# SCH_Victron-Orion-DC-DC-Charger-Cooling-.net
KiCad netlist of a schematic drawn in EasyEDA
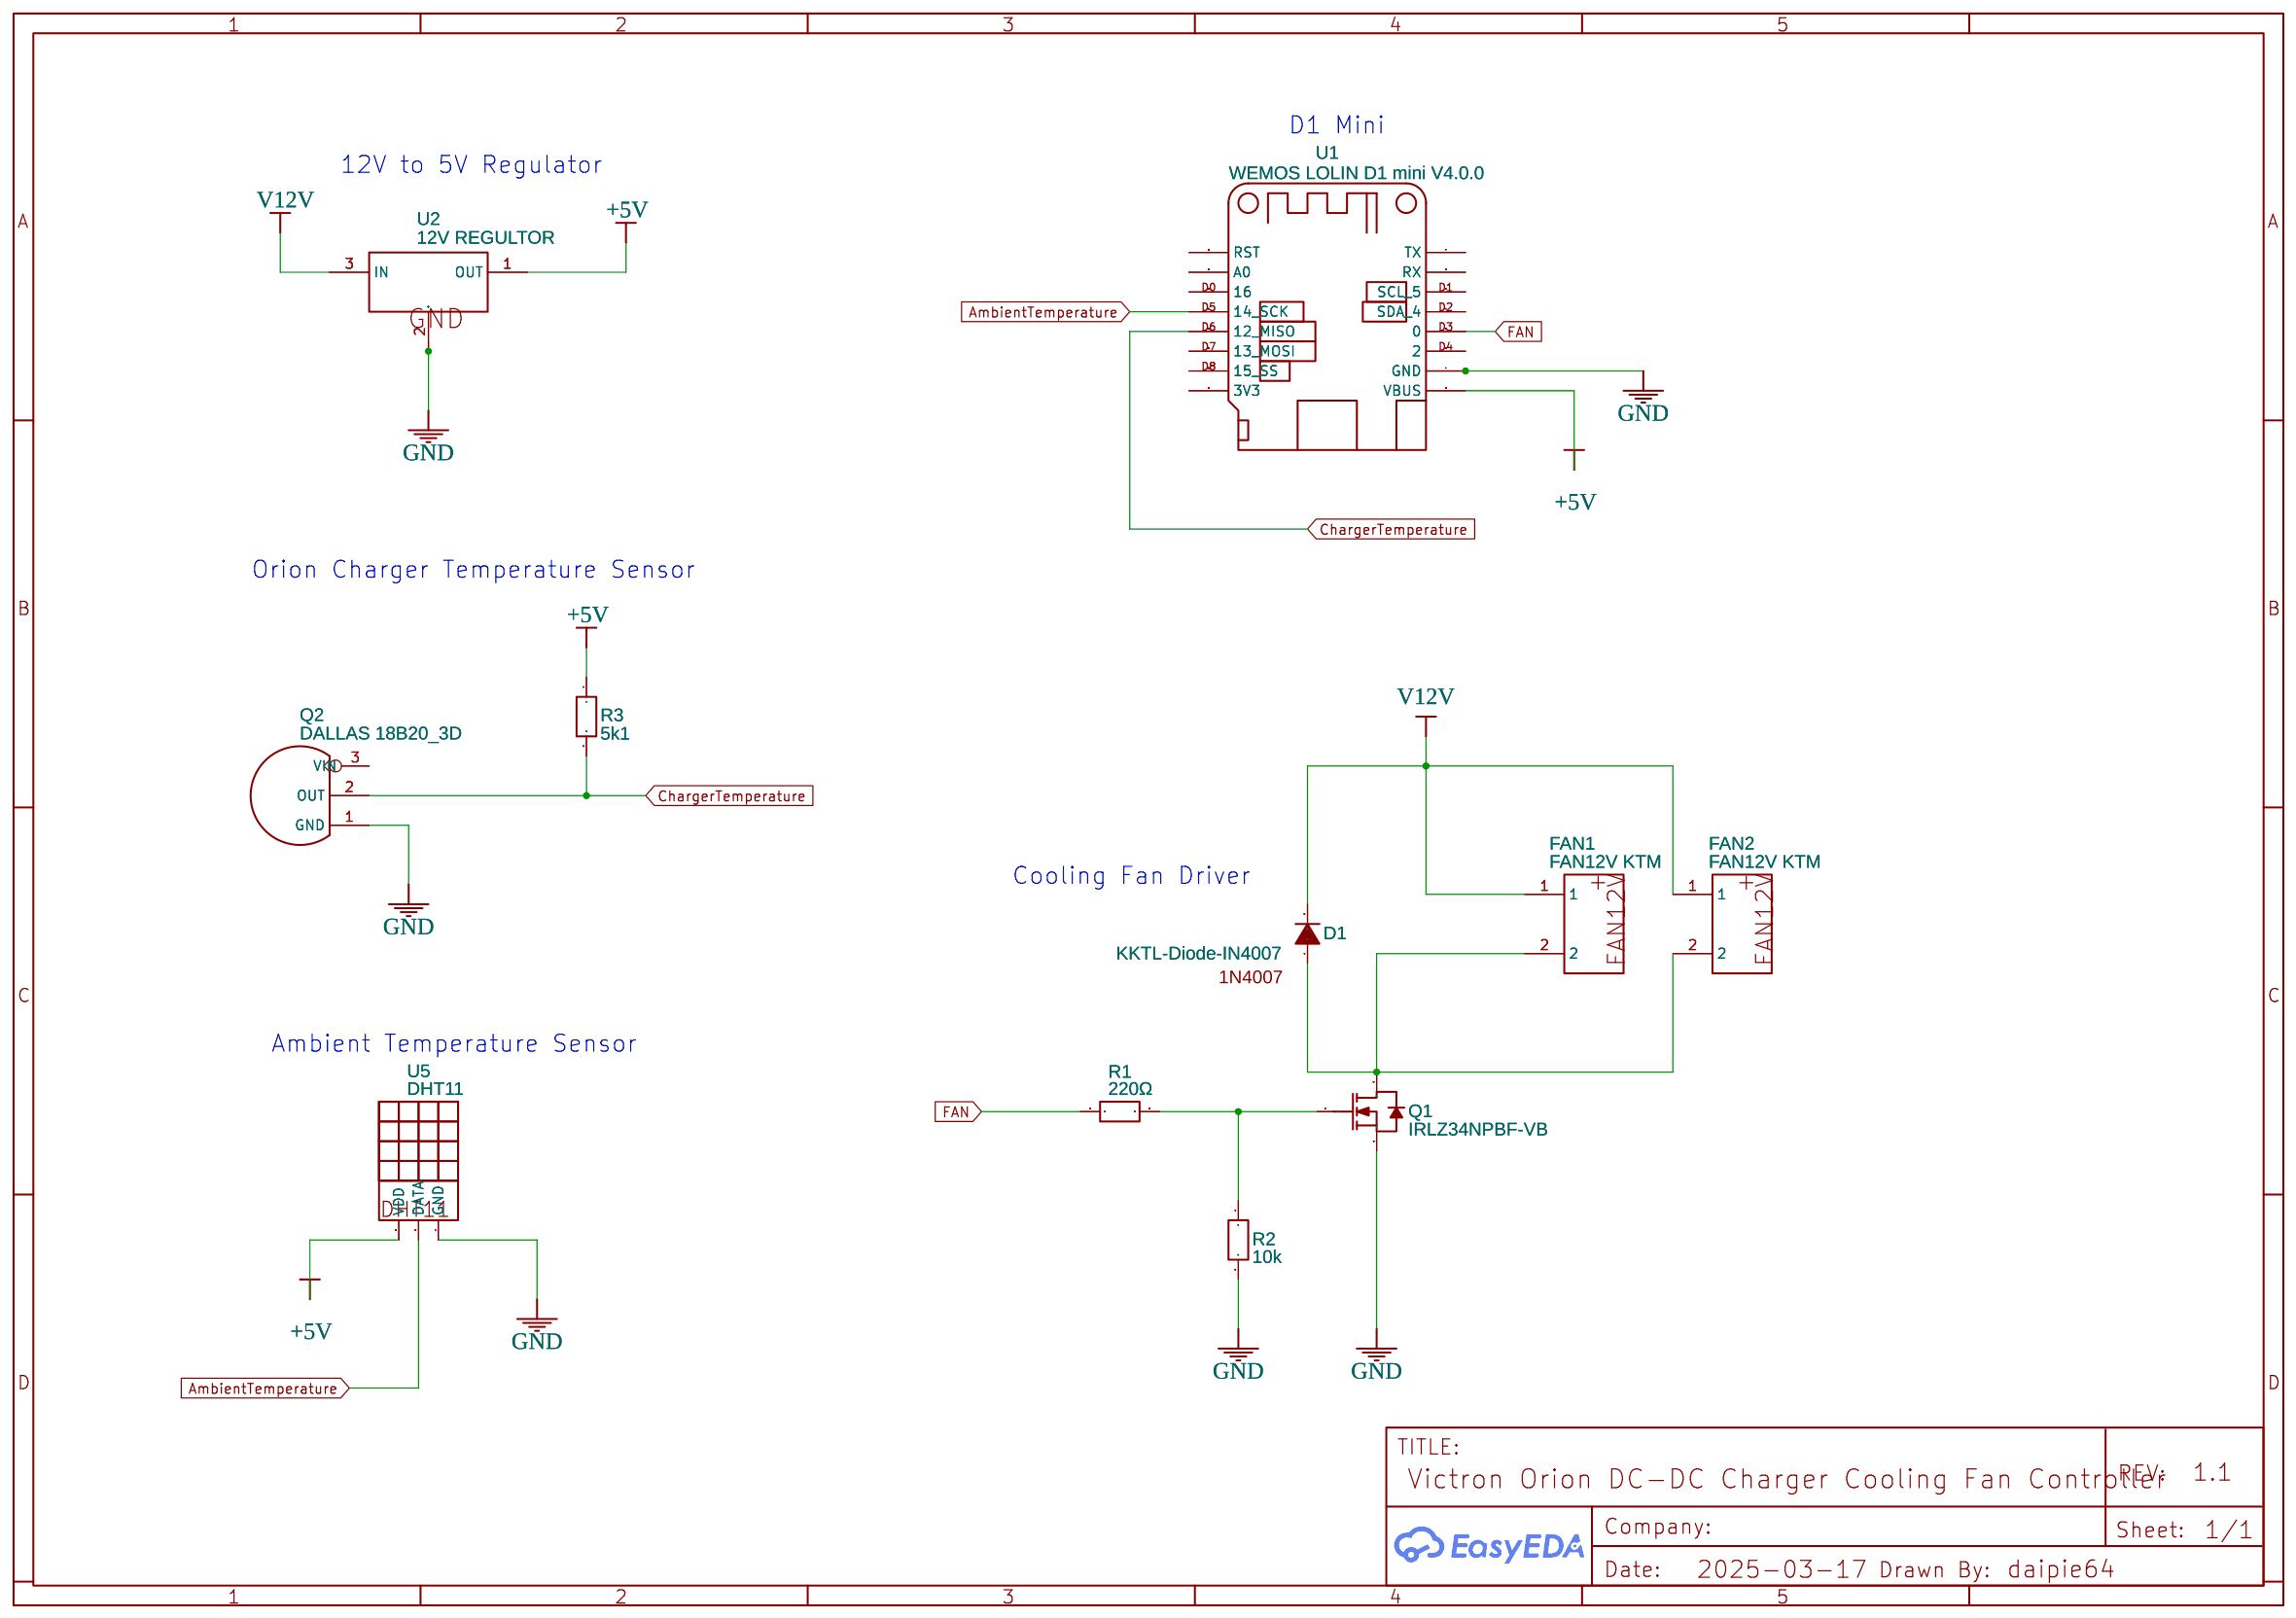
[diagram p0: schematic sheet]

(export (version "E")
  (design (tool "Eeschema 10.0.6"))
  (components
    (comp (ref "D1") (value "KKTL-Diode-IN4007") (libsource (lib "") (part "KKTL-Diode-IN4007")))
    (comp (ref "FAN1")
      (value "FAN12V KTM")
      (fields (field (name "Manufacturer Part") "ktm"))
      (libsource (lib "") (part "FAN12V KTM"))
    )
    (comp (ref "FAN2")
      (value "FAN12V KTM")
      (fields (field (name "Manufacturer Part") "ktm"))
      (libsource (lib "") (part "FAN12V KTM"))
    )
    (comp (ref "Q1")
      (value "IRLZ34NPBF-VB")
      (fields (field (name "Manufacturer") "VBsemi(微碧半导体)"))
      (libsource (lib "") (part "IRLZ34NPBF-VB"))
    )
    (comp (ref "Q2")
      (value "DALLAS 18B20_3D")
      (fields (field (name "Manufacturer Part") "DS18B20"))
      (libsource (lib "") (part "DALLAS 18B20_3D"))
    )
    (comp (ref "R1") (value "220Ω") (libsource (lib "") (part "R_0603_EU")))
    (comp (ref "R2") (value "10k") (libsource (lib "") (part "R_0603_EU_1")))
    (comp (ref "R3") (value "5k1") (libsource (lib "") (part "R_0603_EU_1")))
    (comp (ref "U1")
      (value "WEMOS LOLIN D1 mini V4.0.0")
      (libsource (lib "") (part "WEMOS LOLIN D1 mini V4.0.0"))
    )
    (comp (ref "U2")
      (value "12V REGULTOR")
      (fields (field (name "Manufacturer Part") "CJ78L05") (field (name "Manufacturer") "CJ"))
      (libsource (lib "") (part "7805(SOT-89)"))
    )
    (comp (ref "U5") (value "DHT11") (libsource (lib "") (part "DHT11")))
  )
  (nets
    (net (code "1") (name "+5V") (class "Default")
      (node (ref "R3") (pin "1") (pinfunction "1_1") (pintype "unspecified"))
      (node (ref "U1") (pin "8") (pinfunction "VBUS_8") (pintype "unspecified"))
      (node (ref "U2") (pin "1") (pinfunction "OUT_1") (pintype "passive"))
      (node (ref "U5") (pin "3") (pinfunction "VDD_3") (pintype "unspecified"))
    )
    (net (code "2") (name "AmbientTemperature") (class "Default")
      (node (ref "U1") (pin "12") (pinfunction "14_SCK_12") (pintype "unspecified"))
      (node (ref "U5") (pin "2") (pinfunction "DATA_2") (pintype "unspecified"))
    )
    (net (code "3") (name "ChargerTemperature") (class "Default")
      (node (ref "Q2") (pin "2") (pinfunction "OUT_2") (pintype "unspecified"))
      (node (ref "R3") (pin "2") (pinfunction "2_2") (pintype "unspecified"))
      (node (ref "U1") (pin "13") (pinfunction "12_MISO_13") (pintype "unspecified"))
    )
    (net (code "4") (name "FAN") (class "Default")
      (node (ref "R1") (pin "1") (pinfunction "1_1") (pintype "unspecified"))
      (node (ref "U1") (pin "5") (pinfunction "0_5") (pintype "unspecified"))
    )
    (net (code "5") (name "GND") (class "Default")
      (node (ref "Q1") (pin "3") (pinfunction "S_3") (pintype "unspecified"))
      (node (ref "Q2") (pin "1") (pinfunction "GND_1") (pintype "unspecified"))
      (node (ref "R2") (pin "2") (pinfunction "2_2") (pintype "unspecified"))
      (node (ref "U1") (pin "7") (pinfunction "GND_7") (pintype "unspecified"))
      (node (ref "U2") (pin "2") (pinfunction "GND_2") (pintype "passive"))
      (node (ref "U5") (pin "1") (pinfunction "GND_1") (pintype "unspecified"))
    )
    (net (code "6") (name "Net-(Q1-D)") (class "Default")
      (node (ref "D1") (pin "1") (pinfunction "1_1") (pintype "input"))
      (node (ref "FAN1") (pin "2") (pinfunction "2_2") (pintype "unspecified"))
      (node (ref "FAN2") (pin "2") (pinfunction "2_2") (pintype "unspecified"))
      (node (ref "Q1") (pin "2") (pinfunction "D_2") (pintype "unspecified"))
    )
    (net (code "7") (name "Net-(Q1-G)") (class "Default")
      (node (ref "Q1") (pin "1") (pinfunction "G_1") (pintype "unspecified"))
      (node (ref "R1") (pin "2") (pinfunction "2_2") (pintype "unspecified"))
      (node (ref "R2") (pin "1") (pinfunction "1_1") (pintype "unspecified"))
    )
    (net (code "8") (name "V12V") (class "Default")
      (node (ref "D1") (pin "2") (pinfunction "2_2") (pintype "input"))
      (node (ref "FAN1") (pin "1") (pinfunction "1_1") (pintype "unspecified"))
      (node (ref "FAN2") (pin "1") (pinfunction "1_1") (pintype "unspecified"))
      (node (ref "U2") (pin "3") (pinfunction "IN_3") (pintype "passive"))
    )
    (net (code "9") (name "unconnected-(Q2-VIN-Pad3)") (class "Default")
      (node (ref "Q2") (pin "3") (pinfunction "VIN_3") (pintype "unspecified"))
    )
    (net (code "10") (name "unconnected-(U1-2-Pad6)") (class "Default")
      (node (ref "U1") (pin "6") (pinfunction "2_6") (pintype "unspecified"))
    )
    (net (code "11") (name "unconnected-(U1-3V3-Pad16)") (class "Default")
      (node (ref "U1") (pin "16") (pinfunction "3V3_16") (pintype "unspecified"))
    )
    (net (code "12") (name "unconnected-(U1-13_MOSI-Pad14)") (class "Default")
      (node (ref "U1") (pin "14") (pinfunction "13_MOSI_14") (pintype "unspecified"))
    )
    (net (code "13") (name "unconnected-(U1-15_SS-Pad15)") (class "Default")
      (node (ref "U1") (pin "15") (pinfunction "15_SS_15") (pintype "unspecified"))
    )
    (net (code "14") (name "unconnected-(U1-16-Pad11)") (class "Default")
      (node (ref "U1") (pin "11") (pinfunction "16_11") (pintype "unspecified"))
    )
    (net (code "15") (name "unconnected-(U1-A0-Pad10)") (class "Default")
      (node (ref "U1") (pin "10") (pinfunction "A0_10") (pintype "unspecified"))
    )
    (net (code "16") (name "unconnected-(U1-RST-Pad9)") (class "Default")
      (node (ref "U1") (pin "9") (pinfunction "RST_9") (pintype "unspecified"))
    )
    (net (code "17") (name "unconnected-(U1-RX-Pad2)") (class "Default")
      (node (ref "U1") (pin "2") (pinfunction "RX_2") (pintype "unspecified"))
    )
    (net (code "18") (name "unconnected-(U1-SCL_5-Pad3)") (class "Default")
      (node (ref "U1") (pin "3") (pinfunction "SCL_5_3") (pintype "unspecified"))
    )
    (net (code "19") (name "unconnected-(U1-SDA_4-Pad4)") (class "Default")
      (node (ref "U1") (pin "4") (pinfunction "SDA_4_4") (pintype "unspecified"))
    )
    (net (code "20") (name "unconnected-(U1-TX-Pad1)") (class "Default")
      (node (ref "U1") (pin "1") (pinfunction "TX_1") (pintype "unspecified"))
    )
  )
)
